# eMMC_SD.net
KiCad netlist of a schematic drawn in Altium Designer
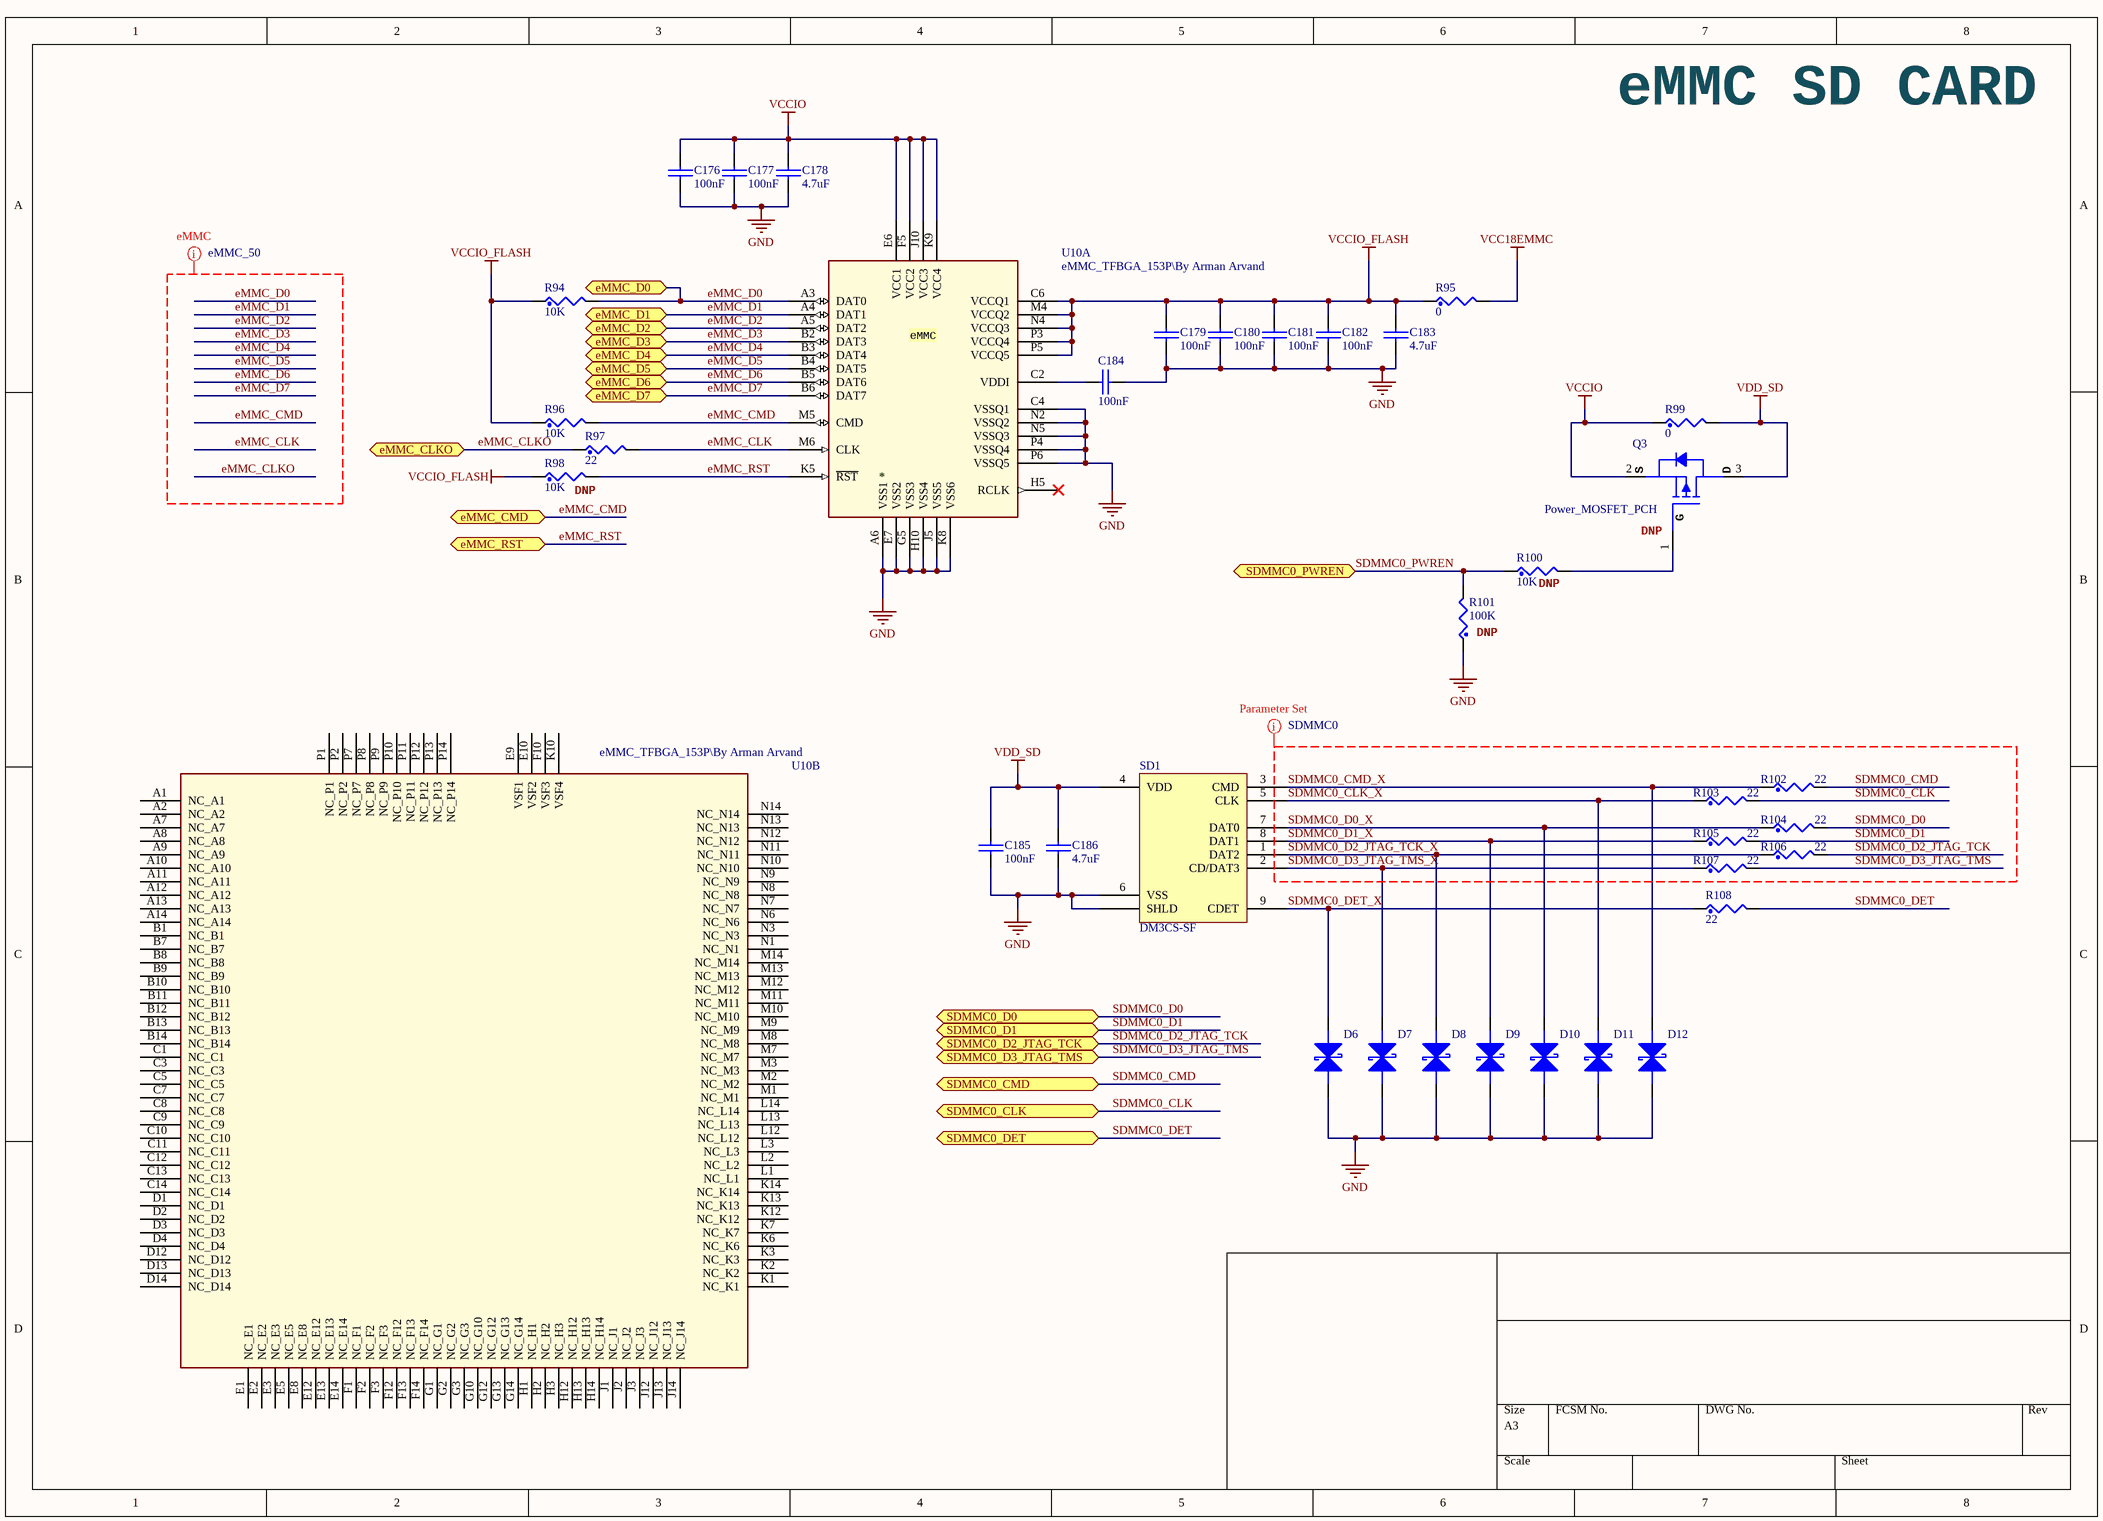
[diagram p0: eMMC_SD.SchDoc]

(export (version "E")
  (design (tool "Eeschema 10.0.6"))
  (components
    (comp (ref "C176")
      (value "100nF")
      (footprint "0402_CC - C")
      (libsource (lib "AAR_RockChip_RK3328") (part "CAP_NP"))
    )
    (comp (ref "C177")
      (value "100nF")
      (footprint "0402_CC - C")
      (libsource (lib "AAR_RockChip_RK3328") (part "CAP_NP"))
    )
    (comp (ref "C178")
      (value "4.7uF")
      (footprint "0603_CC")
      (libsource (lib "AAR_RockChip_RK3328") (part "CAP_NP"))
    )
    (comp (ref "C179")
      (value "100nF")
      (footprint "0402_CC - C")
      (libsource (lib "AAR_RockChip_RK3328") (part "CAP_NP"))
    )
    (comp (ref "C180")
      (value "100nF")
      (footprint "0402_CC - C")
      (libsource (lib "AAR_RockChip_RK3328") (part "CAP_NP"))
    )
    (comp (ref "C181")
      (value "100nF")
      (footprint "0402_CC - C")
      (libsource (lib "AAR_RockChip_RK3328") (part "CAP_NP"))
    )
    (comp (ref "C182")
      (value "100nF")
      (footprint "0402_CC - C")
      (libsource (lib "AAR_RockChip_RK3328") (part "CAP_NP"))
    )
    (comp (ref "C183")
      (value "4.7uF")
      (footprint "0603_CC")
      (libsource (lib "AAR_RockChip_RK3328") (part "CAP_NP"))
    )
    (comp (ref "C184")
      (value "100nF")
      (footprint "0402_CC - C")
      (libsource (lib "AAR_RockChip_RK3328") (part "CAP_NP"))
    )
    (comp (ref "C185")
      (value "100nF")
      (footprint "0402_CC - C")
      (libsource (lib "AAR_RockChip_RK3328") (part "CAP_NP"))
    )
    (comp (ref "C186")
      (value "4.7uF")
      (footprint "0603_CC")
      (libsource (lib "AAR_RockChip_RK3328") (part "CAP_NP"))
    )
    (comp (ref "D6")
      (value "PGB1010603MR")
      (footprint "TVS0603")
      (description "SUPPRESSOR ESD 24VDC 0603 SMD")
      (fields (field (name "MANUFACTURER") "Littelfuse Inc"))
      (libsource (lib "AAR_RockChip_RK3328") (part "PGB1010603MR"))
    )
    (comp (ref "D7")
      (value "PGB1010603MR")
      (footprint "TVS0603")
      (description "SUPPRESSOR ESD 24VDC 0603 SMD")
      (fields (field (name "MANUFACTURER") "Littelfuse Inc"))
      (libsource (lib "AAR_RockChip_RK3328") (part "PGB1010603MR"))
    )
    (comp (ref "D8")
      (value "PGB1010603MR")
      (footprint "TVS0603")
      (description "SUPPRESSOR ESD 24VDC 0603 SMD")
      (fields (field (name "MANUFACTURER") "Littelfuse Inc"))
      (libsource (lib "AAR_RockChip_RK3328") (part "PGB1010603MR"))
    )
    (comp (ref "D9")
      (value "PGB1010603MR")
      (footprint "TVS0603")
      (description "SUPPRESSOR ESD 24VDC 0603 SMD")
      (fields (field (name "MANUFACTURER") "Littelfuse Inc"))
      (libsource (lib "AAR_RockChip_RK3328") (part "PGB1010603MR"))
    )
    (comp (ref "D10")
      (value "PGB1010603MR")
      (footprint "TVS0603")
      (description "SUPPRESSOR ESD 24VDC 0603 SMD")
      (fields (field (name "MANUFACTURER") "Littelfuse Inc"))
      (libsource (lib "AAR_RockChip_RK3328") (part "PGB1010603MR"))
    )
    (comp (ref "D11")
      (value "PGB1010603MR")
      (footprint "TVS0603")
      (description "SUPPRESSOR ESD 24VDC 0603 SMD")
      (fields (field (name "MANUFACTURER") "Littelfuse Inc"))
      (libsource (lib "AAR_RockChip_RK3328") (part "PGB1010603MR"))
    )
    (comp (ref "D12")
      (value "PGB1010603MR")
      (footprint "TVS0603")
      (description "SUPPRESSOR ESD 24VDC 0603 SMD")
      (fields (field (name "MANUFACTURER") "Littelfuse Inc"))
      (libsource (lib "AAR_RockChip_RK3328") (part "PGB1010603MR"))
    )
    (comp (ref "Q3")
      (value "Power_MOSFET_PCH")
      (footprint "SOT95P240X130-3N")
      (description "WPM2015 , Single P-Channel, -20V, -2.4A, Power MOSFET , By Arman Arvand")
      (fields (field (name "MFR_PART_NO") "WPM2015-3/TR") (field (name "LCSC PART #") "C213159"))
      (libsource (lib "AAR_RockChip_RK3328") (part "WPM2015-3/TR"))
    )
    (comp (ref "R94")
      (value "10K")
      (footprint "0402_CR")
      (libsource (lib "AAR_RockChip_RK3328") (part "RES"))
    )
    (comp (ref "R95") (value "0") (footprint "0402_CR") (libsource (lib "AAR_RockChip_RK3328") (part "RES")))
    (comp (ref "R96")
      (value "10K")
      (footprint "0402_CR")
      (libsource (lib "AAR_RockChip_RK3328") (part "RES"))
    )
    (comp (ref "R97") (value "22") (footprint "0402_CR") (libsource (lib "AAR_RockChip_RK3328") (part "RES")))
    (comp (ref "R98")
      (value "10K")
      (footprint "0402_CR")
      (libsource (lib "AAR_RockChip_RK3328") (part "RES"))
    )
    (comp (ref "R99") (value "0") (footprint "0402_CR") (libsource (lib "AAR_RockChip_RK3328") (part "RES")))
    (comp (ref "R100")
      (value "10K")
      (footprint "0402_CR")
      (libsource (lib "AAR_RockChip_RK3328") (part "RES"))
    )
    (comp (ref "R101")
      (value "100K")
      (footprint "0402_CR")
      (libsource (lib "AAR_RockChip_RK3328") (part "RES"))
    )
    (comp (ref "R102")
      (value "22")
      (footprint "0402_CR")
      (libsource (lib "AAR_RockChip_RK3328") (part "RES"))
    )
    (comp (ref "R103")
      (value "22")
      (footprint "0402_CR")
      (libsource (lib "AAR_RockChip_RK3328") (part "RES"))
    )
    (comp (ref "R104")
      (value "22")
      (footprint "0402_CR")
      (libsource (lib "AAR_RockChip_RK3328") (part "RES"))
    )
    (comp (ref "R105")
      (value "22")
      (footprint "0402_CR")
      (libsource (lib "AAR_RockChip_RK3328") (part "RES"))
    )
    (comp (ref "R106")
      (value "22")
      (footprint "0402_CR")
      (libsource (lib "AAR_RockChip_RK3328") (part "RES"))
    )
    (comp (ref "R107")
      (value "22")
      (footprint "0402_CR")
      (libsource (lib "AAR_RockChip_RK3328") (part "RES"))
    )
    (comp (ref "R108")
      (value "22")
      (footprint "0402_CR")
      (libsource (lib "AAR_RockChip_RK3328") (part "RES"))
    )
    (comp (ref "SD1")
      (value "DM3CS-SF")
      (footprint "HIROSE DM3CS")
      (description "CONN MICRO SD CARD HINGED TYPE")
      (fields (field (name "MANUFACTURER") "Hirose Electric Co Ltd"))
      (libsource (lib "Celestial Altium Library - altium_library") (part "Hirose DM3C MicroSD"))
    )
    (comp (ref "U10")
      (value "eMMC_TFBGA_153~{P}By Arman Arvand")
      (footprint "TFBGA153_0P5_11.5X13X1.2")
      (description "MTFC4GMWDM-3M_AIT_A_TFBGA_153P\\By Arman Arvand note!  pin A6 in eMMC V4.51 must be NC(RFU)")
      (libsource (lib "AAR_RockChip_RK3328") (part "MTFC4GMWDM-3M AIT A"))
    )
  )
  (nets
    (net (code "1") (name "/SDMMC0_CLK") (class "Default")
      (node (ref "R103") (pin "2") (pinfunction "2_2") (pintype "passive"))
    )
    (net (code "2") (name "/SDMMC0_CLK_X") (class "Default")
      (node (ref "D11") (pin "1") (pinfunction "1_1") (pintype "passive"))
      (node (ref "R103") (pin "1") (pinfunction "1_1") (pintype "passive"))
      (node (ref "SD1") (pin "5") (pinfunction "CLK_5") (pintype "passive"))
    )
    (net (code "3") (name "/SDMMC0_CMD") (class "Default")
      (node (ref "R102") (pin "2") (pinfunction "2_2") (pintype "passive"))
    )
    (net (code "4") (name "/SDMMC0_CMD_X") (class "Default")
      (node (ref "D12") (pin "1") (pinfunction "1_1") (pintype "passive"))
      (node (ref "R102") (pin "1") (pinfunction "1_1") (pintype "passive"))
      (node (ref "SD1") (pin "3") (pinfunction "CMD_3") (pintype "passive"))
    )
    (net (code "5") (name "/SDMMC0_D0") (class "Default")
      (node (ref "R104") (pin "2") (pinfunction "2_2") (pintype "passive"))
    )
    (net (code "6") (name "/SDMMC0_D0_X") (class "Default")
      (node (ref "D10") (pin "1") (pinfunction "1_1") (pintype "passive"))
      (node (ref "R104") (pin "1") (pinfunction "1_1") (pintype "passive"))
      (node (ref "SD1") (pin "7") (pinfunction "DAT0_7") (pintype "passive"))
    )
    (net (code "7") (name "/SDMMC0_D1") (class "Default")
      (node (ref "R105") (pin "2") (pinfunction "2_2") (pintype "passive"))
    )
    (net (code "8") (name "/SDMMC0_D1_X") (class "Default")
      (node (ref "D9") (pin "1") (pinfunction "1_1") (pintype "passive"))
      (node (ref "R105") (pin "1") (pinfunction "1_1") (pintype "passive"))
      (node (ref "SD1") (pin "8") (pinfunction "DAT1_8") (pintype "passive"))
    )
    (net (code "9") (name "/SDMMC0_D2_JTAG_TCK") (class "Default")
      (node (ref "R106") (pin "2") (pinfunction "2_2") (pintype "passive"))
    )
    (net (code "10") (name "/SDMMC0_D2_JTAG_TCK_X") (class "Default")
      (node (ref "D8") (pin "1") (pinfunction "1_1") (pintype "passive"))
      (node (ref "R106") (pin "1") (pinfunction "1_1") (pintype "passive"))
      (node (ref "SD1") (pin "1") (pinfunction "DAT2_1") (pintype "passive"))
    )
    (net (code "11") (name "/SDMMC0_D3_JTAG_TMS") (class "Default")
      (node (ref "R107") (pin "2") (pinfunction "2_2") (pintype "passive"))
    )
    (net (code "12") (name "/SDMMC0_D3_JTAG_TMS_X") (class "Default")
      (node (ref "D7") (pin "1") (pinfunction "1_1") (pintype "passive"))
      (node (ref "R107") (pin "1") (pinfunction "1_1") (pintype "passive"))
      (node (ref "SD1") (pin "2") (pinfunction "CD/DAT3_2") (pintype "passive"))
    )
    (net (code "13") (name "/SDMMC0_DET") (class "Default")
      (node (ref "R108") (pin "2") (pinfunction "2_2") (pintype "passive"))
    )
    (net (code "14") (name "/SDMMC0_DET_X") (class "Default")
      (node (ref "D6") (pin "1") (pinfunction "1_1") (pintype "passive"))
      (node (ref "R108") (pin "1") (pinfunction "1_1") (pintype "passive"))
      (node (ref "SD1") (pin "9") (pinfunction "CDET_9") (pintype "passive"))
    )
    (net (code "15") (name "/SDMMC0_PWREN") (class "Default")
      (node (ref "R100") (pin "1") (pinfunction "1_1") (pintype "passive"))
      (node (ref "R101") (pin "2") (pinfunction "2_2") (pintype "passive"))
    )
    (net (code "16") (name "/eMMC_CLK") (class "Default")
      (node (ref "R97") (pin "2") (pinfunction "2_2") (pintype "passive"))
      (node (ref "U10") (pin "M6") (pinfunction "CLK_M6") (pintype "input"))
    )
    (net (code "17") (name "/eMMC_CLKO") (class "Default")
      (node (ref "R97") (pin "1") (pinfunction "1_1") (pintype "passive"))
    )
    (net (code "18") (name "/eMMC_CMD") (class "Default")
      (node (ref "R96") (pin "2") (pinfunction "2_2") (pintype "passive"))
      (node (ref "U10") (pin "M5") (pinfunction "CMD_M5") (pintype "bidirectional"))
    )
    (net (code "19") (name "/eMMC_D0") (class "Default")
      (node (ref "R94") (pin "2") (pinfunction "2_2") (pintype "passive"))
      (node (ref "U10") (pin "A3") (pinfunction "DAT0_A3") (pintype "bidirectional"))
    )
    (net (code "20") (name "/eMMC_D1") (class "Default")
      (node (ref "U10") (pin "A4") (pinfunction "DAT1_A4") (pintype "bidirectional"))
    )
    (net (code "21") (name "/eMMC_D2") (class "Default")
      (node (ref "U10") (pin "A5") (pinfunction "DAT2_A5") (pintype "bidirectional"))
    )
    (net (code "22") (name "/eMMC_D3") (class "Default")
      (node (ref "U10") (pin "B2") (pinfunction "DAT3_B2") (pintype "bidirectional"))
    )
    (net (code "23") (name "/eMMC_D4") (class "Default")
      (node (ref "U10") (pin "B3") (pinfunction "DAT4_B3") (pintype "bidirectional"))
    )
    (net (code "24") (name "/eMMC_D5") (class "Default")
      (node (ref "U10") (pin "B4") (pinfunction "DAT5_B4") (pintype "bidirectional"))
    )
    (net (code "25") (name "/eMMC_D6") (class "Default")
      (node (ref "U10") (pin "B5") (pinfunction "DAT6_B5") (pintype "bidirectional"))
    )
    (net (code "26") (name "/eMMC_D7") (class "Default")
      (node (ref "U10") (pin "B6") (pinfunction "DAT7_B6") (pintype "bidirectional"))
    )
    (net (code "27") (name "/eMMC_RST") (class "Default")
      (node (ref "R98") (pin "2") (pinfunction "2_2") (pintype "passive"))
      (node (ref "U10") (pin "K5") (pinfunction "~{RST}_K5") (pintype "input"))
    )
    (net (code "28") (name "GND") (class "Default")
      (node (ref "C176") (pin "2") (pinfunction "2_2") (pintype "passive"))
      (node (ref "C177") (pin "2") (pinfunction "2_2") (pintype "passive"))
      (node (ref "C178") (pin "2") (pinfunction "2_2") (pintype "passive"))
      (node (ref "C179") (pin "2") (pinfunction "2_2") (pintype "passive"))
      (node (ref "C180") (pin "2") (pinfunction "2_2") (pintype "passive"))
      (node (ref "C181") (pin "2") (pinfunction "2_2") (pintype "passive"))
      (node (ref "C182") (pin "2") (pinfunction "2_2") (pintype "passive"))
      (node (ref "C183") (pin "2") (pinfunction "2_2") (pintype "passive"))
      (node (ref "C184") (pin "2") (pinfunction "2_2") (pintype "passive"))
      (node (ref "C185") (pin "2") (pinfunction "2_2") (pintype "passive"))
      (node (ref "C186") (pin "2") (pinfunction "2_2") (pintype "passive"))
      (node (ref "D10") (pin "2") (pinfunction "2_2") (pintype "passive"))
      (node (ref "D11") (pin "2") (pinfunction "2_2") (pintype "passive"))
      (node (ref "D12") (pin "2") (pinfunction "2_2") (pintype "passive"))
      (node (ref "D6") (pin "2") (pinfunction "2_2") (pintype "passive"))
      (node (ref "D7") (pin "2") (pinfunction "2_2") (pintype "passive"))
      (node (ref "D8") (pin "2") (pinfunction "2_2") (pintype "passive"))
      (node (ref "D9") (pin "2") (pinfunction "2_2") (pintype "passive"))
      (node (ref "R101") (pin "1") (pinfunction "1_1") (pintype "passive"))
      (node (ref "SD1") (pin "6") (pinfunction "VSS_6") (pintype "passive"))
      (node (ref "SD1") (pin "S") (pinfunction "SHLD_S") (pintype "passive"))
      (node (ref "U10") (pin "A6") (pinfunction "VSS1_A6") (pintype "power_in"))
      (node (ref "U10") (pin "C4") (pinfunction "VSSQ1_C4") (pintype "power_in"))
      (node (ref "U10") (pin "E7") (pinfunction "VSS2_E7") (pintype "power_in"))
      (node (ref "U10") (pin "G5") (pinfunction "VSS3_G5") (pintype "power_in"))
      (node (ref "U10") (pin "H10") (pinfunction "VSS4_H10") (pintype "power_in"))
      (node (ref "U10") (pin "J5") (pinfunction "VSS5_J5") (pintype "power_in"))
      (node (ref "U10") (pin "K8") (pinfunction "VSS6_K8") (pintype "power_in"))
      (node (ref "U10") (pin "N2") (pinfunction "VSSQ2_N2") (pintype "power_in"))
      (node (ref "U10") (pin "N5") (pinfunction "VSSQ3_N5") (pintype "power_in"))
      (node (ref "U10") (pin "P4") (pinfunction "VSSQ4_P4") (pintype "power_in"))
      (node (ref "U10") (pin "P6") (pinfunction "VSSQ5_P6") (pintype "power_in"))
    )
    (net (code "29") (name "Net-(Q3-Pad1)") (class "Default")
      (node (ref "Q3") (pin "1") (pinfunction "1_1") (pintype "passive"))
      (node (ref "R100") (pin "2") (pinfunction "2_2") (pintype "passive"))
    )
    (net (code "30") (name "Net-(U10A-VDDI)") (class "Default")
      (node (ref "C184") (pin "1") (pinfunction "1_1") (pintype "passive"))
      (node (ref "U10") (pin "C2") (pinfunction "VDDI_C2") (pintype "power_in"))
    )
    (net (code "31") (name "VCC18EMMC") (class "Default")
      (node (ref "R95") (pin "2") (pinfunction "2_2") (pintype "passive"))
    )
    (net (code "32") (name "VCCIO") (class "Default")
      (node (ref "C176") (pin "1") (pinfunction "1_1") (pintype "passive"))
      (node (ref "C177") (pin "1") (pinfunction "1_1") (pintype "passive"))
      (node (ref "C178") (pin "1") (pinfunction "1_1") (pintype "passive"))
      (node (ref "Q3") (pin "2") (pinfunction "2_2") (pintype "passive"))
      (node (ref "R99") (pin "1") (pinfunction "1_1") (pintype "passive"))
      (node (ref "U10") (pin "E6") (pinfunction "VCC1_E6") (pintype "power_in"))
      (node (ref "U10") (pin "F5") (pinfunction "VCC2_F5") (pintype "power_in"))
      (node (ref "U10") (pin "J10") (pinfunction "VCC3_J10") (pintype "power_in"))
      (node (ref "U10") (pin "K9") (pinfunction "VCC4_K9") (pintype "power_in"))
    )
    (net (code "33") (name "VCCIO_FLASH") (class "Default")
      (node (ref "C179") (pin "1") (pinfunction "1_1") (pintype "passive"))
      (node (ref "C180") (pin "1") (pinfunction "1_1") (pintype "passive"))
      (node (ref "C181") (pin "1") (pinfunction "1_1") (pintype "passive"))
      (node (ref "C182") (pin "1") (pinfunction "1_1") (pintype "passive"))
      (node (ref "C183") (pin "1") (pinfunction "1_1") (pintype "passive"))
      (node (ref "R94") (pin "1") (pinfunction "1_1") (pintype "passive"))
      (node (ref "R95") (pin "1") (pinfunction "1_1") (pintype "passive"))
      (node (ref "R96") (pin "1") (pinfunction "1_1") (pintype "passive"))
      (node (ref "R98") (pin "1") (pinfunction "1_1") (pintype "passive"))
      (node (ref "U10") (pin "C6") (pinfunction "VCCQ1_C6") (pintype "power_in"))
      (node (ref "U10") (pin "M4") (pinfunction "VCCQ2_M4") (pintype "power_in"))
      (node (ref "U10") (pin "N4") (pinfunction "VCCQ3_N4") (pintype "power_in"))
      (node (ref "U10") (pin "P3") (pinfunction "VCCQ4_P3") (pintype "power_in"))
      (node (ref "U10") (pin "P5") (pinfunction "VCCQ5_P5") (pintype "power_in"))
    )
    (net (code "34") (name "VDD_SD") (class "Default")
      (node (ref "C185") (pin "1") (pinfunction "1_1") (pintype "passive"))
      (node (ref "C186") (pin "1") (pinfunction "1_1") (pintype "passive"))
      (node (ref "Q3") (pin "3") (pinfunction "3_3") (pintype "passive"))
      (node (ref "R99") (pin "2") (pinfunction "2_2") (pintype "passive"))
      (node (ref "SD1") (pin "4") (pinfunction "VDD_4") (pintype "passive"))
    )
    (net (code "35") (name "unconnected-(U10A-RCLK-PadH5)") (class "Default")
      (node (ref "U10") (pin "H5") (pinfunction "RCLK_H5") (pintype "output+no_connect"))
    )
    (net (code "36") (name "unconnected-(U10B-NC_A1-PadA1)") (class "Default")
      (node (ref "U10") (pin "A1") (pinfunction "NC_A1_A1") (pintype "passive"))
    )
    (net (code "37") (name "unconnected-(U10B-NC_A2-PadA2)") (class "Default")
      (node (ref "U10") (pin "A2") (pinfunction "NC_A2_A2") (pintype "passive"))
    )
    (net (code "38") (name "unconnected-(U10B-NC_A7-PadA7)") (class "Default")
      (node (ref "U10") (pin "A7") (pinfunction "NC_A7_A7") (pintype "passive"))
    )
    (net (code "39") (name "unconnected-(U10B-NC_A8-PadA8)") (class "Default")
      (node (ref "U10") (pin "A8") (pinfunction "NC_A8_A8") (pintype "passive"))
    )
    (net (code "40") (name "unconnected-(U10B-NC_A9-PadA9)") (class "Default")
      (node (ref "U10") (pin "A9") (pinfunction "NC_A9_A9") (pintype "passive"))
    )
    (net (code "41") (name "unconnected-(U10B-NC_A10-PadA10)") (class "Default")
      (node (ref "U10") (pin "A10") (pinfunction "NC_A10_A10") (pintype "passive"))
    )
    (net (code "42") (name "unconnected-(U10B-NC_A11-PadA11)") (class "Default")
      (node (ref "U10") (pin "A11") (pinfunction "NC_A11_A11") (pintype "passive"))
    )
    (net (code "43") (name "unconnected-(U10B-NC_A12-PadA12)") (class "Default")
      (node (ref "U10") (pin "A12") (pinfunction "NC_A12_A12") (pintype "passive"))
    )
    (net (code "44") (name "unconnected-(U10B-NC_A13-PadA13)") (class "Default")
      (node (ref "U10") (pin "A13") (pinfunction "NC_A13_A13") (pintype "passive"))
    )
    (net (code "45") (name "unconnected-(U10B-NC_A14-PadA14)") (class "Default")
      (node (ref "U10") (pin "A14") (pinfunction "NC_A14_A14") (pintype "passive"))
    )
    (net (code "46") (name "unconnected-(U10B-NC_B1-PadB1)") (class "Default")
      (node (ref "U10") (pin "B1") (pinfunction "NC_B1_B1") (pintype "passive"))
    )
    (net (code "47") (name "unconnected-(U10B-NC_B7-PadB7)") (class "Default")
      (node (ref "U10") (pin "B7") (pinfunction "NC_B7_B7") (pintype "passive"))
    )
    (net (code "48") (name "unconnected-(U10B-NC_B8-PadB8)") (class "Default")
      (node (ref "U10") (pin "B8") (pinfunction "NC_B8_B8") (pintype "passive"))
    )
    (net (code "49") (name "unconnected-(U10B-NC_B9-PadB9)") (class "Default")
      (node (ref "U10") (pin "B9") (pinfunction "NC_B9_B9") (pintype "passive"))
    )
    (net (code "50") (name "unconnected-(U10B-NC_B10-PadB10)") (class "Default")
      (node (ref "U10") (pin "B10") (pinfunction "NC_B10_B10") (pintype "passive"))
    )
    (net (code "51") (name "unconnected-(U10B-NC_B11-PadB11)") (class "Default")
      (node (ref "U10") (pin "B11") (pinfunction "NC_B11_B11") (pintype "passive"))
    )
    (net (code "52") (name "unconnected-(U10B-NC_B12-PadB12)") (class "Default")
      (node (ref "U10") (pin "B12") (pinfunction "NC_B12_B12") (pintype "passive"))
    )
    (net (code "53") (name "unconnected-(U10B-NC_B13-PadB13)") (class "Default")
      (node (ref "U10") (pin "B13") (pinfunction "NC_B13_B13") (pintype "passive"))
    )
    (net (code "54") (name "unconnected-(U10B-NC_B14-PadB14)") (class "Default")
      (node (ref "U10") (pin "B14") (pinfunction "NC_B14_B14") (pintype "passive"))
    )
    (net (code "55") (name "unconnected-(U10B-NC_C1-PadC1)") (class "Default")
      (node (ref "U10") (pin "C1") (pinfunction "NC_C1_C1") (pintype "passive"))
    )
    (net (code "56") (name "unconnected-(U10B-NC_C3-PadC3)") (class "Default")
      (node (ref "U10") (pin "C3") (pinfunction "NC_C3_C3") (pintype "passive"))
    )
    (net (code "57") (name "unconnected-(U10B-NC_C5-PadC5)") (class "Default")
      (node (ref "U10") (pin "C5") (pinfunction "NC_C5_C5") (pintype "passive"))
    )
    (net (code "58") (name "unconnected-(U10B-NC_C7-PadC7)") (class "Default")
      (node (ref "U10") (pin "C7") (pinfunction "NC_C7_C7") (pintype "passive"))
    )
    (net (code "59") (name "unconnected-(U10B-NC_C8-PadC8)") (class "Default")
      (node (ref "U10") (pin "C8") (pinfunction "NC_C8_C8") (pintype "passive"))
    )
    (net (code "60") (name "unconnected-(U10B-NC_C9-PadC9)") (class "Default")
      (node (ref "U10") (pin "C9") (pinfunction "NC_C9_C9") (pintype "passive"))
    )
    (net (code "61") (name "unconnected-(U10B-NC_C10-PadC10)") (class "Default")
      (node (ref "U10") (pin "C10") (pinfunction "NC_C10_C10") (pintype "passive"))
    )
    (net (code "62") (name "unconnected-(U10B-NC_C11-PadC11)") (class "Default")
      (node (ref "U10") (pin "C11") (pinfunction "NC_C11_C11") (pintype "passive"))
    )
    (net (code "63") (name "unconnected-(U10B-NC_C12-PadC12)") (class "Default")
      (node (ref "U10") (pin "C12") (pinfunction "NC_C12_C12") (pintype "passive"))
    )
    (net (code "64") (name "unconnected-(U10B-NC_C13-PadC13)") (class "Default")
      (node (ref "U10") (pin "C13") (pinfunction "NC_C13_C13") (pintype "passive"))
    )
    (net (code "65") (name "unconnected-(U10B-NC_C14-PadC14)") (class "Default")
      (node (ref "U10") (pin "C14") (pinfunction "NC_C14_C14") (pintype "passive"))
    )
    (net (code "66") (name "unconnected-(U10B-NC_D1-PadD1)") (class "Default")
      (node (ref "U10") (pin "D1") (pinfunction "NC_D1_D1") (pintype "passive"))
    )
    (net (code "67") (name "unconnected-(U10B-NC_D2-PadD2)") (class "Default")
      (node (ref "U10") (pin "D2") (pinfunction "NC_D2_D2") (pintype "passive"))
    )
    (net (code "68") (name "unconnected-(U10B-NC_D3-PadD3)") (class "Default")
      (node (ref "U10") (pin "D3") (pinfunction "NC_D3_D3") (pintype "passive"))
    )
    (net (code "69") (name "unconnected-(U10B-NC_D4-PadD4)") (class "Default")
      (node (ref "U10") (pin "D4") (pinfunction "NC_D4_D4") (pintype "passive"))
    )
    (net (code "70") (name "unconnected-(U10B-NC_D12-PadD12)") (class "Default")
      (node (ref "U10") (pin "D12") (pinfunction "NC_D12_D12") (pintype "passive"))
    )
    (net (code "71") (name "unconnected-(U10B-NC_D13-PadD13)") (class "Default")
      (node (ref "U10") (pin "D13") (pinfunction "NC_D13_D13") (pintype "passive"))
    )
    (net (code "72") (name "unconnected-(U10B-NC_D14-PadD14)") (class "Default")
      (node (ref "U10") (pin "D14") (pinfunction "NC_D14_D14") (pintype "passive"))
    )
    (net (code "73") (name "unconnected-(U10B-NC_E1-PadE1)") (class "Default")
      (node (ref "U10") (pin "E1") (pinfunction "NC_E1_E1") (pintype "passive"))
    )
    (net (code "74") (name "unconnected-(U10B-NC_E2-PadE2)") (class "Default")
      (node (ref "U10") (pin "E2") (pinfunction "NC_E2_E2") (pintype "passive"))
    )
    (net (code "75") (name "unconnected-(U10B-NC_E3-PadE3)") (class "Default")
      (node (ref "U10") (pin "E3") (pinfunction "NC_E3_E3") (pintype "passive"))
    )
    (net (code "76") (name "unconnected-(U10B-NC_E5-PadE5)") (class "Default")
      (node (ref "U10") (pin "E5") (pinfunction "NC_E5_E5") (pintype "passive"))
    )
    (net (code "77") (name "unconnected-(U10B-NC_E8-PadE8)") (class "Default")
      (node (ref "U10") (pin "E8") (pinfunction "NC_E8_E8") (pintype "passive"))
    )
    (net (code "78") (name "unconnected-(U10B-NC_E12-PadE12)") (class "Default")
      (node (ref "U10") (pin "E12") (pinfunction "NC_E12_E12") (pintype "passive"))
    )
    (net (code "79") (name "unconnected-(U10B-NC_E13-PadE13)") (class "Default")
      (node (ref "U10") (pin "E13") (pinfunction "NC_E13_E13") (pintype "passive"))
    )
    (net (code "80") (name "unconnected-(U10B-NC_E14-PadE14)") (class "Default")
      (node (ref "U10") (pin "E14") (pinfunction "NC_E14_E14") (pintype "passive"))
    )
    (net (code "81") (name "unconnected-(U10B-NC_F1-PadF1)") (class "Default")
      (node (ref "U10") (pin "F1") (pinfunction "NC_F1_F1") (pintype "passive"))
    )
    (net (code "82") (name "unconnected-(U10B-NC_F2-PadF2)") (class "Default")
      (node (ref "U10") (pin "F2") (pinfunction "NC_F2_F2") (pintype "passive"))
    )
    (net (code "83") (name "unconnected-(U10B-NC_F3-PadF3)") (class "Default")
      (node (ref "U10") (pin "F3") (pinfunction "NC_F3_F3") (pintype "passive"))
    )
    (net (code "84") (name "unconnected-(U10B-NC_F12-PadF12)") (class "Default")
      (node (ref "U10") (pin "F12") (pinfunction "NC_F12_F12") (pintype "passive"))
    )
    (net (code "85") (name "unconnected-(U10B-NC_F13-PadF13)") (class "Default")
      (node (ref "U10") (pin "F13") (pinfunction "NC_F13_F13") (pintype "passive"))
    )
    (net (code "86") (name "unconnected-(U10B-NC_F14-PadF14)") (class "Default")
      (node (ref "U10") (pin "F14") (pinfunction "NC_F14_F14") (pintype "passive"))
    )
    (net (code "87") (name "unconnected-(U10B-NC_G1-PadG1)") (class "Default")
      (node (ref "U10") (pin "G1") (pinfunction "NC_G1_G1") (pintype "passive"))
    )
    (net (code "88") (name "unconnected-(U10B-NC_G2-PadG2)") (class "Default")
      (node (ref "U10") (pin "G2") (pinfunction "NC_G2_G2") (pintype "passive"))
    )
    (net (code "89") (name "unconnected-(U10B-NC_G3-PadG3)") (class "Default")
      (node (ref "U10") (pin "G3") (pinfunction "NC_G3_G3") (pintype "passive"))
    )
    (net (code "90") (name "unconnected-(U10B-NC_G10-PadG10)") (class "Default")
      (node (ref "U10") (pin "G10") (pinfunction "NC_G10_G10") (pintype "passive"))
    )
    (net (code "91") (name "unconnected-(U10B-NC_G12-PadG12)") (class "Default")
      (node (ref "U10") (pin "G12") (pinfunction "NC_G12_G12") (pintype "passive"))
    )
    (net (code "92") (name "unconnected-(U10B-NC_G13-PadG13)") (class "Default")
      (node (ref "U10") (pin "G13") (pinfunction "NC_G13_G13") (pintype "passive"))
    )
    (net (code "93") (name "unconnected-(U10B-NC_G14-PadG14)") (class "Default")
      (node (ref "U10") (pin "G14") (pinfunction "NC_G14_G14") (pintype "passive"))
    )
    (net (code "94") (name "unconnected-(U10B-NC_H1-PadH1)") (class "Default")
      (node (ref "U10") (pin "H1") (pinfunction "NC_H1_H1") (pintype "passive"))
    )
    (net (code "95") (name "unconnected-(U10B-NC_H2-PadH2)") (class "Default")
      (node (ref "U10") (pin "H2") (pinfunction "NC_H2_H2") (pintype "passive"))
    )
    (net (code "96") (name "unconnected-(U10B-NC_H3-PadH3)") (class "Default")
      (node (ref "U10") (pin "H3") (pinfunction "NC_H3_H3") (pintype "passive"))
    )
    (net (code "97") (name "unconnected-(U10B-NC_H12-PadH12)") (class "Default")
      (node (ref "U10") (pin "H12") (pinfunction "NC_H12_H12") (pintype "passive"))
    )
    (net (code "98") (name "unconnected-(U10B-NC_H13-PadH13)") (class "Default")
      (node (ref "U10") (pin "H13") (pinfunction "NC_H13_H13") (pintype "passive"))
    )
    (net (code "99") (name "unconnected-(U10B-NC_H14-PadH14)") (class "Default")
      (node (ref "U10") (pin "H14") (pinfunction "NC_H14_H14") (pintype "passive"))
    )
    (net (code "100") (name "unconnected-(U10B-NC_J1-PadJ1)") (class "Default")
      (node (ref "U10") (pin "J1") (pinfunction "NC_J1_J1") (pintype "passive"))
    )
    (net (code "101") (name "unconnected-(U10B-NC_J2-PadJ2)") (class "Default")
      (node (ref "U10") (pin "J2") (pinfunction "NC_J2_J2") (pintype "passive"))
    )
    (net (code "102") (name "unconnected-(U10B-NC_J3-PadJ3)") (class "Default")
      (node (ref "U10") (pin "J3") (pinfunction "NC_J3_J3") (pintype "passive"))
    )
    (net (code "103") (name "unconnected-(U10B-NC_J12-PadJ12)") (class "Default")
      (node (ref "U10") (pin "J12") (pinfunction "NC_J12_J12") (pintype "passive"))
    )
    (net (code "104") (name "unconnected-(U10B-NC_J13-PadJ13)") (class "Default")
      (node (ref "U10") (pin "J13") (pinfunction "NC_J13_J13") (pintype "passive"))
    )
    (net (code "105") (name "unconnected-(U10B-NC_J14-PadJ14)") (class "Default")
      (node (ref "U10") (pin "J14") (pinfunction "NC_J14_J14") (pintype "passive"))
    )
    (net (code "106") (name "unconnected-(U10B-NC_K1-PadK1)") (class "Default")
      (node (ref "U10") (pin "K1") (pinfunction "NC_K1_K1") (pintype "passive"))
    )
    (net (code "107") (name "unconnected-(U10B-NC_K2-PadK2)") (class "Default")
      (node (ref "U10") (pin "K2") (pinfunction "NC_K2_K2") (pintype "passive"))
    )
    (net (code "108") (name "unconnected-(U10B-NC_K3-PadK3)") (class "Default")
      (node (ref "U10") (pin "K3") (pinfunction "NC_K3_K3") (pintype "passive"))
    )
    (net (code "109") (name "unconnected-(U10B-NC_K6-PadK6)") (class "Default")
      (node (ref "U10") (pin "K6") (pinfunction "NC_K6_K6") (pintype "passive"))
    )
    (net (code "110") (name "unconnected-(U10B-NC_K7-PadK7)") (class "Default")
      (node (ref "U10") (pin "K7") (pinfunction "NC_K7_K7") (pintype "passive"))
    )
    (net (code "111") (name "unconnected-(U10B-NC_K12-PadK12)") (class "Default")
      (node (ref "U10") (pin "K12") (pinfunction "NC_K12_K12") (pintype "passive"))
    )
    (net (code "112") (name "unconnected-(U10B-NC_K13-PadK13)") (class "Default")
      (node (ref "U10") (pin "K13") (pinfunction "NC_K13_K13") (pintype "passive"))
    )
    (net (code "113") (name "unconnected-(U10B-NC_K14-PadK14)") (class "Default")
      (node (ref "U10") (pin "K14") (pinfunction "NC_K14_K14") (pintype "passive"))
    )
    (net (code "114") (name "unconnected-(U10B-NC_L1-PadL1)") (class "Default")
      (node (ref "U10") (pin "L1") (pinfunction "NC_L1_L1") (pintype "passive"))
    )
    (net (code "115") (name "unconnected-(U10B-NC_L2-PadL2)") (class "Default")
      (node (ref "U10") (pin "L2") (pinfunction "NC_L2_L2") (pintype "passive"))
    )
    (net (code "116") (name "unconnected-(U10B-NC_L3-PadL3)") (class "Default")
      (node (ref "U10") (pin "L3") (pinfunction "NC_L3_L3") (pintype "passive"))
    )
    (net (code "117") (name "unconnected-(U10B-NC_L12-PadL12)") (class "Default")
      (node (ref "U10") (pin "L12") (pinfunction "NC_L12_L12") (pintype "passive"))
    )
    (net (code "118") (name "unconnected-(U10B-NC_L13-PadL13)") (class "Default")
      (node (ref "U10") (pin "L13") (pinfunction "NC_L13_L13") (pintype "passive"))
    )
    (net (code "119") (name "unconnected-(U10B-NC_L14-PadL14)") (class "Default")
      (node (ref "U10") (pin "L14") (pinfunction "NC_L14_L14") (pintype "passive"))
    )
    (net (code "120") (name "unconnected-(U10B-NC_M1-PadM1)") (class "Default")
      (node (ref "U10") (pin "M1") (pinfunction "NC_M1_M1") (pintype "passive"))
    )
    (net (code "121") (name "unconnected-(U10B-NC_M2-PadM2)") (class "Default")
      (node (ref "U10") (pin "M2") (pinfunction "NC_M2_M2") (pintype "passive"))
    )
    (net (code "122") (name "unconnected-(U10B-NC_M3-PadM3)") (class "Default")
      (node (ref "U10") (pin "M3") (pinfunction "NC_M3_M3") (pintype "passive"))
    )
    (net (code "123") (name "unconnected-(U10B-NC_M7-PadM7)") (class "Default")
      (node (ref "U10") (pin "M7") (pinfunction "NC_M7_M7") (pintype "passive"))
    )
    (net (code "124") (name "unconnected-(U10B-NC_M8-PadM8)") (class "Default")
      (node (ref "U10") (pin "M8") (pinfunction "NC_M8_M8") (pintype "passive"))
    )
    (net (code "125") (name "unconnected-(U10B-NC_M9-PadM9)") (class "Default")
      (node (ref "U10") (pin "M9") (pinfunction "NC_M9_M9") (pintype "passive"))
    )
    (net (code "126") (name "unconnected-(U10B-NC_M10-PadM10)") (class "Default")
      (node (ref "U10") (pin "M10") (pinfunction "NC_M10_M10") (pintype "passive"))
    )
    (net (code "127") (name "unconnected-(U10B-NC_M11-PadM11)") (class "Default")
      (node (ref "U10") (pin "M11") (pinfunction "NC_M11_M11") (pintype "passive"))
    )
    (net (code "128") (name "unconnected-(U10B-NC_M12-PadM12)") (class "Default")
      (node (ref "U10") (pin "M12") (pinfunction "NC_M12_M12") (pintype "passive"))
    )
    (net (code "129") (name "unconnected-(U10B-NC_M13-PadM13)") (class "Default")
      (node (ref "U10") (pin "M13") (pinfunction "NC_M13_M13") (pintype "passive"))
    )
    (net (code "130") (name "unconnected-(U10B-NC_M14-PadM14)") (class "Default")
      (node (ref "U10") (pin "M14") (pinfunction "NC_M14_M14") (pintype "passive"))
    )
    (net (code "131") (name "unconnected-(U10B-NC_N1-PadN1)") (class "Default")
      (node (ref "U10") (pin "N1") (pinfunction "NC_N1_N1") (pintype "passive"))
    )
    (net (code "132") (name "unconnected-(U10B-NC_N3-PadN3)") (class "Default")
      (node (ref "U10") (pin "N3") (pinfunction "NC_N3_N3") (pintype "passive"))
    )
    (net (code "133") (name "unconnected-(U10B-NC_N6-PadN6)") (class "Default")
      (node (ref "U10") (pin "N6") (pinfunction "NC_N6_N6") (pintype "passive"))
    )
    (net (code "134") (name "unconnected-(U10B-NC_N7-PadN7)") (class "Default")
      (node (ref "U10") (pin "N7") (pinfunction "NC_N7_N7") (pintype "passive"))
    )
    (net (code "135") (name "unconnected-(U10B-NC_N8-PadN8)") (class "Default")
      (node (ref "U10") (pin "N8") (pinfunction "NC_N8_N8") (pintype "passive"))
    )
    (net (code "136") (name "unconnected-(U10B-NC_N9-PadN9)") (class "Default")
      (node (ref "U10") (pin "N9") (pinfunction "NC_N9_N9") (pintype "passive"))
    )
    (net (code "137") (name "unconnected-(U10B-NC_N10-PadN10)") (class "Default")
      (node (ref "U10") (pin "N10") (pinfunction "NC_N10_N10") (pintype "passive"))
    )
    (net (code "138") (name "unconnected-(U10B-NC_N11-PadN11)") (class "Default")
      (node (ref "U10") (pin "N11") (pinfunction "NC_N11_N11") (pintype "passive"))
    )
    (net (code "139") (name "unconnected-(U10B-NC_N12-PadN12)") (class "Default")
      (node (ref "U10") (pin "N12") (pinfunction "NC_N12_N12") (pintype "passive"))
    )
    (net (code "140") (name "unconnected-(U10B-NC_N13-PadN13)") (class "Default")
      (node (ref "U10") (pin "N13") (pinfunction "NC_N13_N13") (pintype "passive"))
    )
    (net (code "141") (name "unconnected-(U10B-NC_N14-PadN14)") (class "Default")
      (node (ref "U10") (pin "N14") (pinfunction "NC_N14_N14") (pintype "passive"))
    )
    (net (code "142") (name "unconnected-(U10B-NC_P1-PadP1)") (class "Default")
      (node (ref "U10") (pin "P1") (pinfunction "NC_P1_P1") (pintype "passive"))
    )
    (net (code "143") (name "unconnected-(U10B-NC_P2-PadP2)") (class "Default")
      (node (ref "U10") (pin "P2") (pinfunction "NC_P2_P2") (pintype "passive"))
    )
    (net (code "144") (name "unconnected-(U10B-NC_P7-PadP7)") (class "Default")
      (node (ref "U10") (pin "P7") (pinfunction "NC_P7_P7") (pintype "passive"))
    )
    (net (code "145") (name "unconnected-(U10B-NC_P8-PadP8)") (class "Default")
      (node (ref "U10") (pin "P8") (pinfunction "NC_P8_P8") (pintype "passive"))
    )
    (net (code "146") (name "unconnected-(U10B-NC_P9-PadP9)") (class "Default")
      (node (ref "U10") (pin "P9") (pinfunction "NC_P9_P9") (pintype "passive"))
    )
    (net (code "147") (name "unconnected-(U10B-NC_P10-PadP10)") (class "Default")
      (node (ref "U10") (pin "P10") (pinfunction "NC_P10_P10") (pintype "passive"))
    )
    (net (code "148") (name "unconnected-(U10B-NC_P11-PadP11)") (class "Default")
      (node (ref "U10") (pin "P11") (pinfunction "NC_P11_P11") (pintype "passive"))
    )
    (net (code "149") (name "unconnected-(U10B-NC_P12-PadP12)") (class "Default")
      (node (ref "U10") (pin "P12") (pinfunction "NC_P12_P12") (pintype "passive"))
    )
    (net (code "150") (name "unconnected-(U10B-NC_P13-PadP13)") (class "Default")
      (node (ref "U10") (pin "P13") (pinfunction "NC_P13_P13") (pintype "passive"))
    )
    (net (code "151") (name "unconnected-(U10B-NC_P14-PadP14)") (class "Default")
      (node (ref "U10") (pin "P14") (pinfunction "NC_P14_P14") (pintype "passive"))
    )
    (net (code "152") (name "unconnected-(U10B-VSF1-PadE9)") (class "Default")
      (node (ref "U10") (pin "E9") (pinfunction "VSF1_E9") (pintype "passive"))
    )
    (net (code "153") (name "unconnected-(U10B-VSF2-PadE10)") (class "Default")
      (node (ref "U10") (pin "E10") (pinfunction "VSF2_E10") (pintype "passive"))
    )
    (net (code "154") (name "unconnected-(U10B-VSF3-PadF10)") (class "Default")
      (node (ref "U10") (pin "F10") (pinfunction "VSF3_F10") (pintype "passive"))
    )
    (net (code "155") (name "unconnected-(U10B-VSF4-PadK10)") (class "Default")
      (node (ref "U10") (pin "K10") (pinfunction "VSF4_K10") (pintype "passive"))
    )
  )
)
